# Receiver.net
KiCad netlist of a schematic drawn in EAGLE
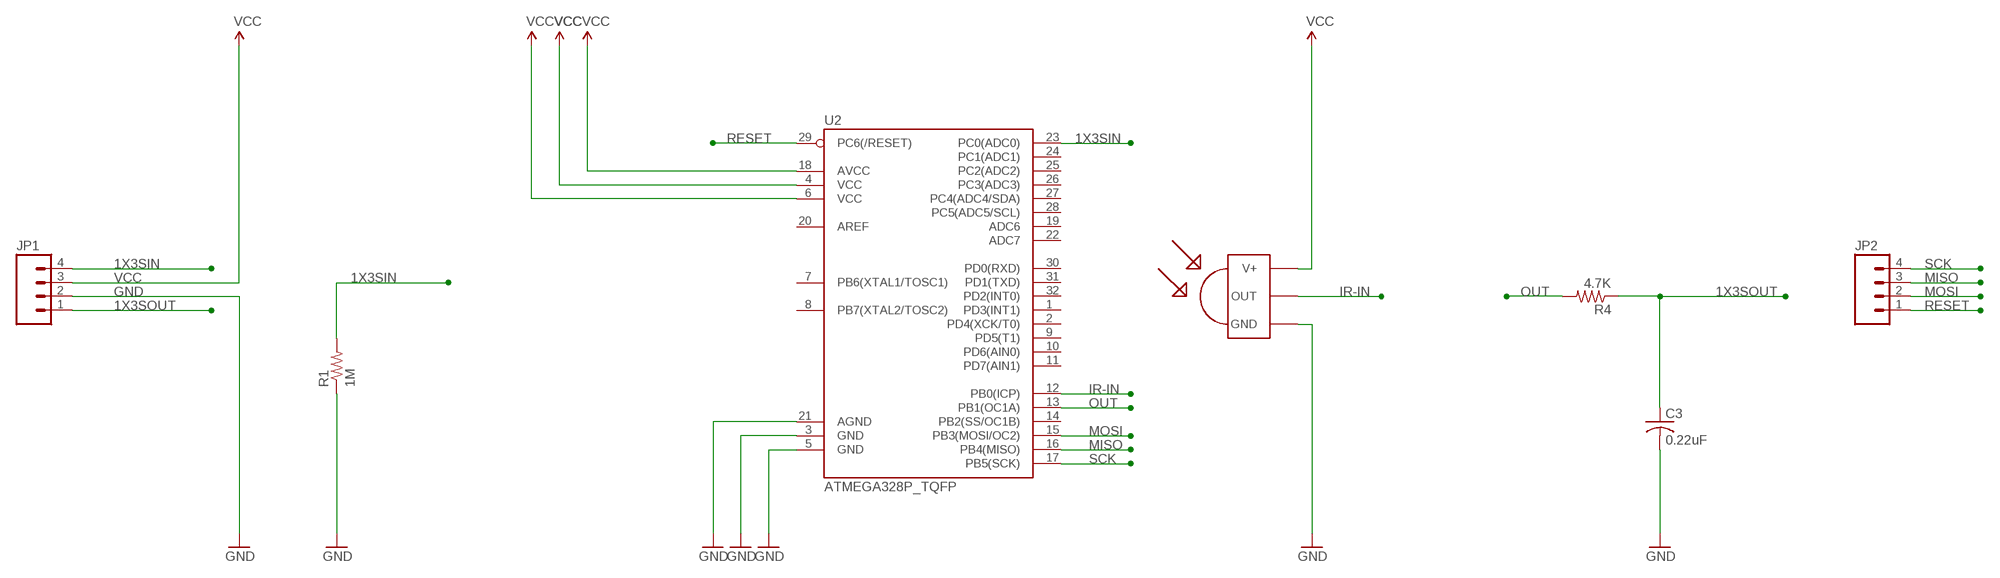
[diagram p0: schematic, sheet 1]

(export (version "E")
  (design (tool "Eeschema 10.0.6"))
  (components
    (comp (ref "C3")
      (value "0.22uF")
      (footprint "eagle-import:C0603")
      (libsource (lib "eagle-import") (part "C-USC0603"))
    )
    (comp (ref "JP1")
      (value "M04PTH")
      (footprint "eagle-import:1X04")
      (libsource (lib "eagle-import") (part "M04PTH"))
    )
    (comp (ref "JP2")
      (value "M04PTH")
      (footprint "eagle-import:1X04")
      (libsource (lib "eagle-import") (part "M04PTH"))
    )
    (comp (ref "R1")
      (value "1M")
      (footprint "eagle-import:R0603")
      (libsource (lib "eagle-import") (part "R-US_R0603"))
    )
    (comp (ref "R4")
      (value "4.7K")
      (footprint "eagle-import:R0603")
      (libsource (lib "eagle-import") (part "R-US_R0603"))
    )
    (comp (ref "U$1")
      (value "IR-RECEIVER")
      (footprint "eagle-import:TSOP382XX,384XX")
      (libsource (lib "eagle-import") (part "IR-RECEIVER"))
    )
    (comp (ref "U2")
      (value "ATMEGA328P_TQFP")
      (footprint "eagle-import:TQFP32-08")
      (libsource (lib "eagle-import") (part "ATMEGA328P_TQFP"))
    )
  )
  (nets
    (net (code "1") (name "/1X3SIN") (class "Default")
      (node (ref "JP1") (pin "4") (pinfunction "4_4") (pintype "passive"))
      (node (ref "R1") (pin "2") (pinfunction "2_2") (pintype "passive"))
      (node (ref "U2") (pin "23") (pinfunction "PC0(ADC0)_23") (pintype "bidirectional"))
    )
    (net (code "2") (name "/1X3SOUT") (class "Default")
      (node (ref "C3") (pin "1") (pinfunction "1_1") (pintype "passive"))
      (node (ref "JP1") (pin "1") (pinfunction "1_1") (pintype "passive"))
      (node (ref "R4") (pin "1") (pinfunction "1_1") (pintype "passive"))
    )
    (net (code "3") (name "/IR-IN") (class "Default")
      (node (ref "U$1") (pin "OUT") (pinfunction "OUT_OUT") (pintype "bidirectional"))
      (node (ref "U2") (pin "12") (pinfunction "PB0(ICP)_12") (pintype "bidirectional"))
    )
    (net (code "4") (name "/MISO") (class "Default")
      (node (ref "JP2") (pin "3") (pinfunction "3_3") (pintype "passive"))
      (node (ref "U2") (pin "16") (pinfunction "PB4(MISO)_16") (pintype "bidirectional"))
    )
    (net (code "5") (name "/MOSI") (class "Default")
      (node (ref "JP2") (pin "2") (pinfunction "2_2") (pintype "passive"))
      (node (ref "U2") (pin "15") (pinfunction "PB3(MOSI/OC2)_15") (pintype "bidirectional"))
    )
    (net (code "6") (name "/OUT") (class "Default")
      (node (ref "R4") (pin "2") (pinfunction "2_2") (pintype "passive"))
      (node (ref "U2") (pin "13") (pinfunction "PB1(OC1A)_13") (pintype "bidirectional"))
    )
    (net (code "7") (name "/RESET") (class "Default")
      (node (ref "JP2") (pin "1") (pinfunction "1_1") (pintype "passive"))
      (node (ref "U2") (pin "29") (pinfunction "PC6(/RESET)_29") (pintype "bidirectional"))
    )
    (net (code "8") (name "/SCK") (class "Default")
      (node (ref "JP2") (pin "4") (pinfunction "4_4") (pintype "passive"))
      (node (ref "U2") (pin "17") (pinfunction "PB5(SCK)_17") (pintype "bidirectional"))
    )
    (net (code "9") (name "GND") (class "Default")
      (node (ref "C3") (pin "2") (pinfunction "2_2") (pintype "passive"))
      (node (ref "JP1") (pin "2") (pinfunction "2_2") (pintype "passive"))
      (node (ref "R1") (pin "1") (pinfunction "1_1") (pintype "passive"))
      (node (ref "U$1") (pin "GND") (pinfunction "GND_GND") (pintype "bidirectional"))
      (node (ref "U2") (pin "21") (pinfunction "AGND_21") (pintype "bidirectional"))
      (node (ref "U2") (pin "3") (pinfunction "GND_3") (pintype "bidirectional"))
      (node (ref "U2") (pin "5") (pinfunction "GND_5") (pintype "bidirectional"))
    )
    (net (code "10") (name "VCC") (class "Default")
      (node (ref "JP1") (pin "3") (pinfunction "3_3") (pintype "passive"))
      (node (ref "U$1") (pin "VSS") (pinfunction "V+_VSS") (pintype "bidirectional"))
      (node (ref "U2") (pin "18") (pinfunction "AVCC_18") (pintype "bidirectional"))
      (node (ref "U2") (pin "4") (pinfunction "VCC_4") (pintype "bidirectional"))
      (node (ref "U2") (pin "6") (pinfunction "VCC_6") (pintype "bidirectional"))
    )
    (net (code "11") (name "unconnected-(U2-ADC6-Pad19)") (class "Default")
      (node (ref "U2") (pin "19") (pinfunction "ADC6_19") (pintype "bidirectional"))
    )
    (net (code "12") (name "unconnected-(U2-ADC7-Pad22)") (class "Default")
      (node (ref "U2") (pin "22") (pinfunction "ADC7_22") (pintype "bidirectional"))
    )
    (net (code "13") (name "unconnected-(U2-AREF-Pad20)") (class "Default")
      (node (ref "U2") (pin "20") (pinfunction "AREF_20") (pintype "bidirectional"))
    )
    (net (code "14") (name "unconnected-(U2-PB2(SS{slash}OC1B)-Pad14)") (class "Default")
      (node (ref "U2") (pin "14") (pinfunction "PB2(SS/OC1B)_14") (pintype "bidirectional"))
    )
    (net (code "15") (name "unconnected-(U2-PB6(XTAL1{slash}TOSC1)-Pad7)") (class "Default")
      (node (ref "U2") (pin "7") (pinfunction "PB6(XTAL1/TOSC1)_7") (pintype "bidirectional"))
    )
    (net (code "16") (name "unconnected-(U2-PB7(XTAL2{slash}TOSC2)-Pad8)") (class "Default")
      (node (ref "U2") (pin "8") (pinfunction "PB7(XTAL2/TOSC2)_8") (pintype "bidirectional"))
    )
    (net (code "17") (name "unconnected-(U2-PC1(ADC1)-Pad24)") (class "Default")
      (node (ref "U2") (pin "24") (pinfunction "PC1(ADC1)_24") (pintype "bidirectional"))
    )
    (net (code "18") (name "unconnected-(U2-PC2(ADC2)-Pad25)") (class "Default")
      (node (ref "U2") (pin "25") (pinfunction "PC2(ADC2)_25") (pintype "bidirectional"))
    )
    (net (code "19") (name "unconnected-(U2-PC3(ADC3)-Pad26)") (class "Default")
      (node (ref "U2") (pin "26") (pinfunction "PC3(ADC3)_26") (pintype "bidirectional"))
    )
    (net (code "20") (name "unconnected-(U2-PC4(ADC4{slash}SDA)-Pad27)") (class "Default")
      (node (ref "U2") (pin "27") (pinfunction "PC4(ADC4/SDA)_27") (pintype "bidirectional"))
    )
    (net (code "21") (name "unconnected-(U2-PC5(ADC5{slash}SCL)-Pad28)") (class "Default")
      (node (ref "U2") (pin "28") (pinfunction "PC5(ADC5/SCL)_28") (pintype "bidirectional"))
    )
    (net (code "22") (name "unconnected-(U2-PD0(RXD)-Pad30)") (class "Default")
      (node (ref "U2") (pin "30") (pinfunction "PD0(RXD)_30") (pintype "bidirectional"))
    )
    (net (code "23") (name "unconnected-(U2-PD1(TXD)-Pad31)") (class "Default")
      (node (ref "U2") (pin "31") (pinfunction "PD1(TXD)_31") (pintype "bidirectional"))
    )
    (net (code "24") (name "unconnected-(U2-PD2(INT0)-Pad32)") (class "Default")
      (node (ref "U2") (pin "32") (pinfunction "PD2(INT0)_32") (pintype "bidirectional"))
    )
    (net (code "25") (name "unconnected-(U2-PD3(INT1)-Pad1)") (class "Default")
      (node (ref "U2") (pin "1") (pinfunction "PD3(INT1)_1") (pintype "bidirectional"))
    )
    (net (code "26") (name "unconnected-(U2-PD4(XCK{slash}T0)-Pad2)") (class "Default")
      (node (ref "U2") (pin "2") (pinfunction "PD4(XCK/T0)_2") (pintype "bidirectional"))
    )
    (net (code "27") (name "unconnected-(U2-PD5(T1)-Pad9)") (class "Default")
      (node (ref "U2") (pin "9") (pinfunction "PD5(T1)_9") (pintype "bidirectional"))
    )
    (net (code "28") (name "unconnected-(U2-PD6(AIN0)-Pad10)") (class "Default")
      (node (ref "U2") (pin "10") (pinfunction "PD6(AIN0)_10") (pintype "bidirectional"))
    )
    (net (code "29") (name "unconnected-(U2-PD7(AIN1)-Pad11)") (class "Default")
      (node (ref "U2") (pin "11") (pinfunction "PD7(AIN1)_11") (pintype "bidirectional"))
    )
  )
)
